# usblcd.net
KiCad netlist of a schematic drawn in EAGLE
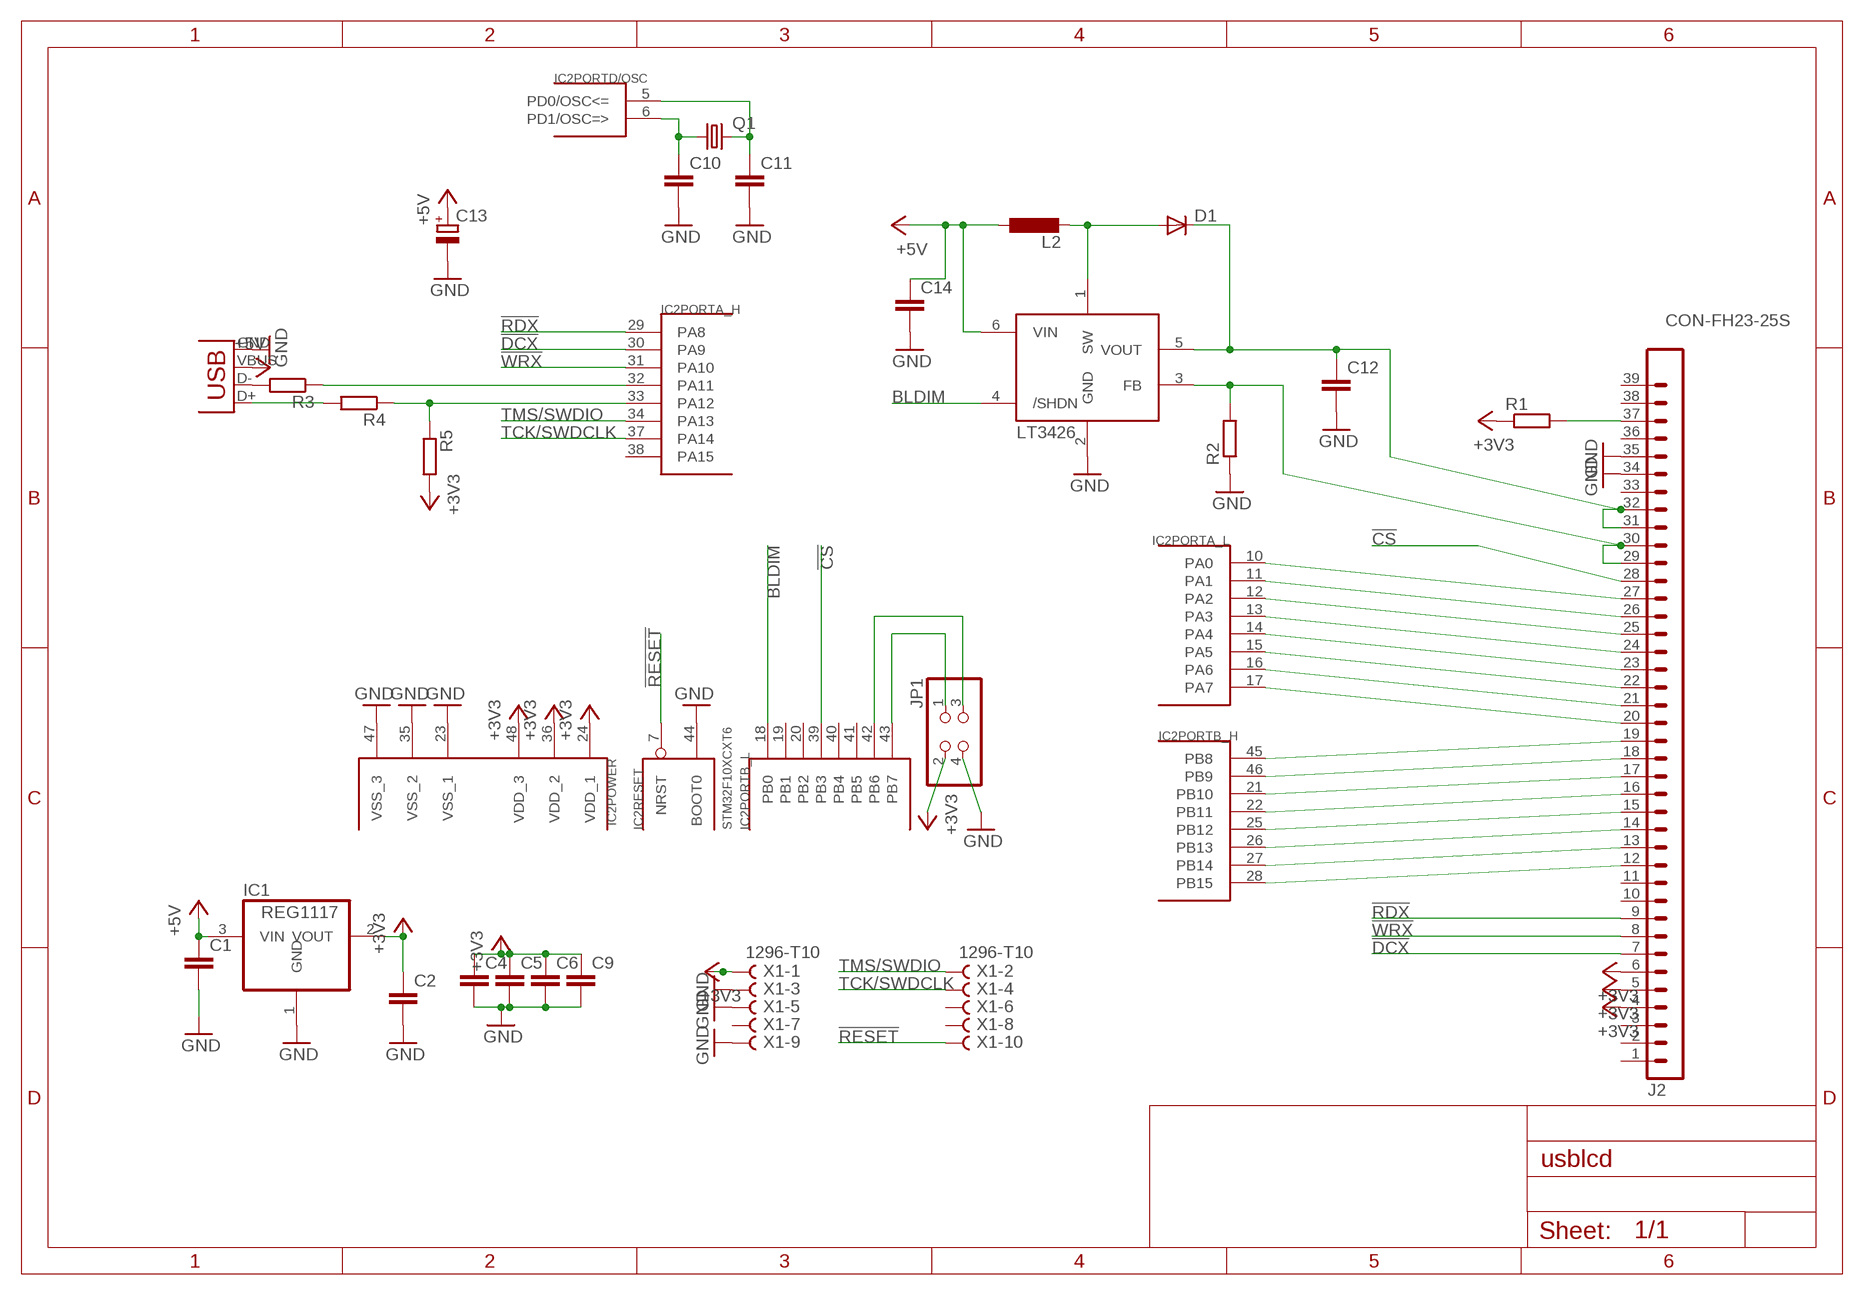
[diagram p0: schematic, sheet 1]

(export (version "E")
  (design (tool "Eeschema 10.0.6"))
  (components
    (comp (ref "C1")
      (value "C-EUC0603")
      (footprint "eagle-import:C0603")
      (libsource (lib "eagle-import") (part "C-EUC0603"))
    )
    (comp (ref "C2")
      (value "C-EUC0603")
      (footprint "eagle-import:C0603")
      (libsource (lib "eagle-import") (part "C-EUC0603"))
    )
    (comp (ref "C4")
      (value "C-EUC0603")
      (footprint "eagle-import:C0603")
      (libsource (lib "eagle-import") (part "C-EUC0603"))
    )
    (comp (ref "C5")
      (value "C-EUC0805")
      (footprint "eagle-import:C0805")
      (libsource (lib "eagle-import") (part "C-EUC0805"))
    )
    (comp (ref "C6")
      (value "C-EUC0603")
      (footprint "eagle-import:C0603")
      (libsource (lib "eagle-import") (part "C-EUC0603"))
    )
    (comp (ref "C9")
      (value "C-EUC0603")
      (footprint "eagle-import:C0603")
      (libsource (lib "eagle-import") (part "C-EUC0603"))
    )
    (comp (ref "C10")
      (value "C-EUC0603")
      (footprint "eagle-import:C0603")
      (libsource (lib "eagle-import") (part "C-EUC0603"))
    )
    (comp (ref "C11")
      (value "C-EUC0603")
      (footprint "eagle-import:C0603")
      (libsource (lib "eagle-import") (part "C-EUC0603"))
    )
    (comp (ref "C12")
      (value "C-EUC0805")
      (footprint "eagle-import:C0805")
      (libsource (lib "eagle-import") (part "C-EUC0805"))
    )
    (comp (ref "C13")
      (value "CPOL-EUC")
      (footprint "eagle-import:PANASONIC_C")
      (libsource (lib "eagle-import") (part "CPOL-EUC"))
    )
    (comp (ref "C14")
      (value "C-EUC0603")
      (footprint "eagle-import:C0603")
      (libsource (lib "eagle-import") (part "C-EUC0603"))
    )
    (comp (ref "D1")
      (value "DIODE-SOD323-W")
      (footprint "eagle-import:SOD323-W")
      (libsource (lib "eagle-import") (part "DIODE-SOD323-W"))
    )
    (comp (ref "IC1")
      (value "REG1117")
      (footprint "eagle-import:SOT223")
      (libsource (lib "eagle-import") (part "REG1117"))
    )
    (comp (ref "IC2")
      (value "STM32F10XCXT6")
      (footprint "eagle-import:TQFP48")
      (libsource (lib "eagle-import") (part "STM32F10XCXT6"))
    )
    (comp (ref "J2")
      (value "CON-FH23-25S")
      (footprint "eagle-import:FH23-25S")
      (libsource (lib "eagle-import") (part "CON-FH23-25S"))
    )
    (comp (ref "JP1")
      (value "PINHD-2X2_2.54-SMD")
      (footprint "eagle-import:2X02SMD")
      (libsource (lib "eagle-import") (part "PINHD-2X2_2.54-SMD"))
    )
    (comp (ref "L2")
      (value "L-EUL3230M")
      (footprint "eagle-import:L3230M")
      (libsource (lib "eagle-import") (part "L-EUL3230M"))
    )
    (comp (ref "Q1")
      (value "CRYSTALCTS406")
      (footprint "eagle-import:CTS406")
      (libsource (lib "eagle-import") (part "CRYSTALCTS406"))
    )
    (comp (ref "R1")
      (value "R-EU_R0603")
      (footprint "eagle-import:R0603")
      (libsource (lib "eagle-import") (part "R-EU_R0603"))
    )
    (comp (ref "R2")
      (value "R-EU_R0603")
      (footprint "eagle-import:R0603")
      (libsource (lib "eagle-import") (part "R-EU_R0603"))
    )
    (comp (ref "R3")
      (value "R-EU_R0603")
      (footprint "eagle-import:R0603")
      (libsource (lib "eagle-import") (part "R-EU_R0603"))
    )
    (comp (ref "R4")
      (value "R-EU_R0603")
      (footprint "eagle-import:R0603")
      (libsource (lib "eagle-import") (part "R-EU_R0603"))
    )
    (comp (ref "R5")
      (value "R-EU_R0603")
      (footprint "eagle-import:R0603")
      (libsource (lib "eagle-import") (part "R-EU_R0603"))
    )
    (comp (ref "U$4")
      (value "LT3426")
      (footprint "eagle-import:SOT23-6")
      (libsource (lib "eagle-import") (part "LT3426"))
    )
    (comp (ref "X1")
      (value "1296-T10")
      (footprint "eagle-import:1296-10")
      (libsource (lib "eagle-import") (part "1296-T10"))
    )
    (comp (ref "X2")
      (value "USB-MICROB")
      (footprint "eagle-import:USB-MICROB")
      (libsource (lib "eagle-import") (part "USB-MICROB"))
    )
  )
  (nets
    (net (code "1") (name "+3V3") (class "Default")
      (node (ref "C2") (pin "1") (pinfunction "1_1") (pintype "passive"))
      (node (ref "C4") (pin "1") (pinfunction "1_1") (pintype "passive"))
      (node (ref "C5") (pin "1") (pinfunction "1_1") (pintype "passive"))
      (node (ref "C6") (pin "1") (pinfunction "1_1") (pintype "passive"))
      (node (ref "C9") (pin "1") (pinfunction "1_1") (pintype "passive"))
      (node (ref "IC1") (pin "2") (pinfunction "VOUT_2") (pintype "output"))
      (node (ref "IC2") (pin "24") (pinfunction "VDD_1_24") (pintype "power_in"))
      (node (ref "IC2") (pin "36") (pinfunction "VDD_2_36") (pintype "power_in"))
      (node (ref "IC2") (pin "48") (pinfunction "VDD_3_48") (pintype "power_in"))
      (node (ref "J2") (pin "4") (pinfunction "4_4") (pintype "passive"))
      (node (ref "J2") (pin "5") (pinfunction "5_5") (pintype "passive"))
      (node (ref "J2") (pin "6") (pinfunction "6_6") (pintype "passive"))
      (node (ref "JP1") (pin "2") (pinfunction "2_2") (pintype "passive"))
      (node (ref "R1") (pin "1") (pinfunction "1_1") (pintype "passive"))
      (node (ref "R5") (pin "2") (pinfunction "2_2") (pintype "passive"))
      (node (ref "X1") (pin "1") (pinfunction "B_1") (pintype "passive"))
    )
    (net (code "2") (name "+5V") (class "Default")
      (node (ref "C1") (pin "1") (pinfunction "1_1") (pintype "passive"))
      (node (ref "C13") (pin "+") (pinfunction "+_+") (pintype "passive"))
      (node (ref "C14") (pin "1") (pinfunction "1_1") (pintype "passive"))
      (node (ref "IC1") (pin "3") (pinfunction "VIN_3") (pintype "input"))
      (node (ref "L2") (pin "1") (pinfunction "1_1") (pintype "passive"))
      (node (ref "U$4") (pin "6") (pinfunction "VIN_6") (pintype "input"))
      (node (ref "X2") (pin "VBUS") (pinfunction "VBUS_VBUS") (pintype "bidirectional"))
    )
    (net (code "3") (name "/BLDIM") (class "Default")
      (node (ref "IC2") (pin "18") (pinfunction "PB0_18") (pintype "bidirectional"))
      (node (ref "U$4") (pin "4") (pinfunction "/SHDN_4") (pintype "input"))
    )
    (net (code "4") (name "/TCK{slash}SWDCLK") (class "Default")
      (node (ref "IC2") (pin "37") (pinfunction "PA14_37") (pintype "bidirectional"))
      (node (ref "X1") (pin "4") (pinfunction "B_4") (pintype "passive"))
    )
    (net (code "5") (name "/TMS{slash}SWDIO") (class "Default")
      (node (ref "IC2") (pin "34") (pinfunction "PA13_34") (pintype "bidirectional"))
      (node (ref "X1") (pin "2") (pinfunction "B_2") (pintype "passive"))
    )
    (net (code "6") (name "/~{CS}") (class "Default")
      (node (ref "IC2") (pin "39") (pinfunction "PB3_39") (pintype "bidirectional"))
      (node (ref "J2") (pin "28") (pinfunction "28_28") (pintype "passive"))
    )
    (net (code "7") (name "/~{DCX}") (class "Default")
      (node (ref "IC2") (pin "30") (pinfunction "PA9_30") (pintype "bidirectional"))
      (node (ref "J2") (pin "7") (pinfunction "7_7") (pintype "passive"))
    )
    (net (code "8") (name "/~{RDX}") (class "Default")
      (node (ref "IC2") (pin "29") (pinfunction "PA8_29") (pintype "bidirectional"))
      (node (ref "J2") (pin "9") (pinfunction "9_9") (pintype "passive"))
    )
    (net (code "9") (name "/~{RESET}") (class "Default")
      (node (ref "IC2") (pin "7") (pinfunction "NRST_7") (pintype "input"))
      (node (ref "X1") (pin "10") (pinfunction "B_10") (pintype "passive"))
    )
    (net (code "10") (name "/~{WRX}") (class "Default")
      (node (ref "IC2") (pin "31") (pinfunction "PA10_31") (pintype "bidirectional"))
      (node (ref "J2") (pin "8") (pinfunction "8_8") (pintype "passive"))
    )
    (net (code "11") (name "GND") (class "Default")
      (node (ref "C1") (pin "2") (pinfunction "2_2") (pintype "passive"))
      (node (ref "C10") (pin "2") (pinfunction "2_2") (pintype "passive"))
      (node (ref "C11") (pin "2") (pinfunction "2_2") (pintype "passive"))
      (node (ref "C12") (pin "2") (pinfunction "2_2") (pintype "passive"))
      (node (ref "C13") (pin "-") (pinfunction "-_-") (pintype "passive"))
      (node (ref "C14") (pin "2") (pinfunction "2_2") (pintype "passive"))
      (node (ref "C2") (pin "2") (pinfunction "2_2") (pintype "passive"))
      (node (ref "C4") (pin "2") (pinfunction "2_2") (pintype "passive"))
      (node (ref "C5") (pin "2") (pinfunction "2_2") (pintype "passive"))
      (node (ref "C6") (pin "2") (pinfunction "2_2") (pintype "passive"))
      (node (ref "C9") (pin "2") (pinfunction "2_2") (pintype "passive"))
      (node (ref "IC1") (pin "1") (pinfunction "GND_1") (pintype "power_in"))
      (node (ref "IC2") (pin "23") (pinfunction "VSS_1_23") (pintype "power_in"))
      (node (ref "IC2") (pin "35") (pinfunction "VSS_2_35") (pintype "power_in"))
      (node (ref "IC2") (pin "44") (pinfunction "BOOT0_44") (pintype "input"))
      (node (ref "IC2") (pin "47") (pinfunction "VSS_3_47") (pintype "power_in"))
      (node (ref "J2") (pin "34") (pinfunction "34_34") (pintype "passive"))
      (node (ref "J2") (pin "35") (pinfunction "35_35") (pintype "passive"))
      (node (ref "JP1") (pin "4") (pinfunction "4_4") (pintype "passive"))
      (node (ref "R2") (pin "1") (pinfunction "1_1") (pintype "passive"))
      (node (ref "U$4") (pin "2") (pinfunction "GND_2") (pintype "power_in"))
      (node (ref "X1") (pin "3") (pinfunction "B_3") (pintype "passive"))
      (node (ref "X1") (pin "5") (pinfunction "B_5") (pintype "passive"))
      (node (ref "X1") (pin "9") (pinfunction "B_9") (pintype "passive"))
      (node (ref "X2") (pin "GND") (pinfunction "GND_GND") (pintype "bidirectional"))
    )
    (net (code "12") (name "Net-(IC2B-PA11)") (class "Default")
      (node (ref "IC2") (pin "32") (pinfunction "PA11_32") (pintype "bidirectional"))
      (node (ref "R3") (pin "1") (pinfunction "1_1") (pintype "passive"))
    )
    (net (code "13") (name "Net-(IC2B-PA12)") (class "Default")
      (node (ref "IC2") (pin "33") (pinfunction "PA12_33") (pintype "bidirectional"))
      (node (ref "R4") (pin "1") (pinfunction "1_1") (pintype "passive"))
      (node (ref "R5") (pin "1") (pinfunction "1_1") (pintype "passive"))
    )
    (net (code "14") (name "Net-(IC2C-PA0)") (class "Default")
      (node (ref "IC2") (pin "10") (pinfunction "PA0_10") (pintype "bidirectional"))
      (node (ref "J2") (pin "27") (pinfunction "27_27") (pintype "passive"))
    )
    (net (code "15") (name "Net-(IC2C-PA1)") (class "Default")
      (node (ref "IC2") (pin "11") (pinfunction "PA1_11") (pintype "bidirectional"))
      (node (ref "J2") (pin "26") (pinfunction "26_26") (pintype "passive"))
    )
    (net (code "16") (name "Net-(IC2C-PA2)") (class "Default")
      (node (ref "IC2") (pin "12") (pinfunction "PA2_12") (pintype "bidirectional"))
      (node (ref "J2") (pin "25") (pinfunction "25_25") (pintype "passive"))
    )
    (net (code "17") (name "Net-(IC2C-PA3)") (class "Default")
      (node (ref "IC2") (pin "13") (pinfunction "PA3_13") (pintype "bidirectional"))
      (node (ref "J2") (pin "24") (pinfunction "24_24") (pintype "passive"))
    )
    (net (code "18") (name "Net-(IC2C-PA4)") (class "Default")
      (node (ref "IC2") (pin "14") (pinfunction "PA4_14") (pintype "bidirectional"))
      (node (ref "J2") (pin "23") (pinfunction "23_23") (pintype "passive"))
    )
    (net (code "19") (name "Net-(IC2C-PA5)") (class "Default")
      (node (ref "IC2") (pin "15") (pinfunction "PA5_15") (pintype "bidirectional"))
      (node (ref "J2") (pin "22") (pinfunction "22_22") (pintype "passive"))
    )
    (net (code "20") (name "Net-(IC2C-PA6)") (class "Default")
      (node (ref "IC2") (pin "16") (pinfunction "PA6_16") (pintype "bidirectional"))
      (node (ref "J2") (pin "21") (pinfunction "21_21") (pintype "passive"))
    )
    (net (code "21") (name "Net-(IC2C-PA7)") (class "Default")
      (node (ref "IC2") (pin "17") (pinfunction "PA7_17") (pintype "bidirectional"))
      (node (ref "J2") (pin "20") (pinfunction "20_20") (pintype "passive"))
    )
    (net (code "22") (name "Net-(IC2D-PB8)") (class "Default")
      (node (ref "IC2") (pin "45") (pinfunction "PB8_45") (pintype "bidirectional"))
      (node (ref "J2") (pin "19") (pinfunction "19_19") (pintype "passive"))
    )
    (net (code "23") (name "Net-(IC2D-PB9)") (class "Default")
      (node (ref "IC2") (pin "46") (pinfunction "PB9_46") (pintype "bidirectional"))
      (node (ref "J2") (pin "18") (pinfunction "18_18") (pintype "passive"))
    )
    (net (code "24") (name "Net-(IC2D-PB10)") (class "Default")
      (node (ref "IC2") (pin "21") (pinfunction "PB10_21") (pintype "bidirectional"))
      (node (ref "J2") (pin "17") (pinfunction "17_17") (pintype "passive"))
    )
    (net (code "25") (name "Net-(IC2D-PB11)") (class "Default")
      (node (ref "IC2") (pin "22") (pinfunction "PB11_22") (pintype "bidirectional"))
      (node (ref "J2") (pin "16") (pinfunction "16_16") (pintype "passive"))
    )
    (net (code "26") (name "Net-(IC2D-PB12)") (class "Default")
      (node (ref "IC2") (pin "25") (pinfunction "PB12_25") (pintype "bidirectional"))
      (node (ref "J2") (pin "15") (pinfunction "15_15") (pintype "passive"))
    )
    (net (code "27") (name "Net-(IC2D-PB13)") (class "Default")
      (node (ref "IC2") (pin "26") (pinfunction "PB13_26") (pintype "bidirectional"))
      (node (ref "J2") (pin "14") (pinfunction "14_14") (pintype "passive"))
    )
    (net (code "28") (name "Net-(IC2D-PB14)") (class "Default")
      (node (ref "IC2") (pin "27") (pinfunction "PB14_27") (pintype "bidirectional"))
      (node (ref "J2") (pin "13") (pinfunction "13_13") (pintype "passive"))
    )
    (net (code "29") (name "Net-(IC2D-PB15)") (class "Default")
      (node (ref "IC2") (pin "28") (pinfunction "PB15_28") (pintype "bidirectional"))
      (node (ref "J2") (pin "12") (pinfunction "12_12") (pintype "passive"))
    )
    (net (code "30") (name "Net-(IC2E-PB6)") (class "Default")
      (node (ref "IC2") (pin "42") (pinfunction "PB6_42") (pintype "bidirectional"))
      (node (ref "JP1") (pin "3") (pinfunction "3_3") (pintype "passive"))
    )
    (net (code "31") (name "Net-(IC2E-PB7)") (class "Default")
      (node (ref "IC2") (pin "43") (pinfunction "PB7_43") (pintype "bidirectional"))
      (node (ref "JP1") (pin "1") (pinfunction "1_1") (pintype "passive"))
    )
    (net (code "32") (name "Net-(IC2G-PD0{slash}OSC<=)") (class "Default")
      (node (ref "C11") (pin "1") (pinfunction "1_1") (pintype "passive"))
      (node (ref "IC2") (pin "5") (pinfunction "PD0/OSC<=_5") (pintype "bidirectional"))
      (node (ref "Q1") (pin "3") (pinfunction "2_3") (pintype "passive"))
    )
    (net (code "33") (name "Net-(IC2G-PD1{slash}OSC=>)") (class "Default")
      (node (ref "C10") (pin "1") (pinfunction "1_1") (pintype "passive"))
      (node (ref "IC2") (pin "6") (pinfunction "PD1/OSC=>_6") (pintype "bidirectional"))
      (node (ref "Q1") (pin "1") (pinfunction "1_1") (pintype "passive"))
    )
    (net (code "34") (name "Net-(J2-Pad37)") (class "Default")
      (node (ref "J2") (pin "37") (pinfunction "37_37") (pintype "passive"))
      (node (ref "R1") (pin "2") (pinfunction "2_2") (pintype "passive"))
    )
    (net (code "35") (name "Net-(R3-Pad2)") (class "Default")
      (node (ref "R3") (pin "2") (pinfunction "2_2") (pintype "passive"))
      (node (ref "X2") (pin "D-") (pinfunction "D-_D-") (pintype "bidirectional"))
    )
    (net (code "36") (name "Net-(R4-Pad2)") (class "Default")
      (node (ref "R4") (pin "2") (pinfunction "2_2") (pintype "passive"))
      (node (ref "X2") (pin "D+") (pinfunction "D+_D+") (pintype "bidirectional"))
    )
    (net (code "37") (name "Net-(U$4-FB)") (class "Default")
      (node (ref "J2") (pin "29") (pinfunction "29_29") (pintype "passive"))
      (node (ref "J2") (pin "30") (pinfunction "30_30") (pintype "passive"))
      (node (ref "R2") (pin "2") (pinfunction "2_2") (pintype "passive"))
      (node (ref "U$4") (pin "3") (pinfunction "FB_3") (pintype "input"))
    )
    (net (code "38") (name "Net-(U$4-SW)") (class "Default")
      (node (ref "D1") (pin "A") (pinfunction "A_A") (pintype "passive"))
      (node (ref "L2") (pin "2") (pinfunction "2_2") (pintype "passive"))
      (node (ref "U$4") (pin "1") (pinfunction "SW_1") (pintype "output"))
    )
    (net (code "39") (name "Net-(U$4-VOUT)") (class "Default")
      (node (ref "C12") (pin "1") (pinfunction "1_1") (pintype "passive"))
      (node (ref "D1") (pin "C") (pinfunction "C_C") (pintype "passive"))
      (node (ref "J2") (pin "31") (pinfunction "31_31") (pintype "passive"))
      (node (ref "J2") (pin "32") (pinfunction "32_32") (pintype "passive"))
      (node (ref "U$4") (pin "5") (pinfunction "VOUT_5") (pintype "output"))
    )
    (net (code "40") (name "unconnected-(IC2B-PA15-Pad38)") (class "Default")
      (node (ref "IC2") (pin "38") (pinfunction "PA15_38") (pintype "bidirectional"))
    )
    (net (code "41") (name "unconnected-(IC2E-PB1-Pad19)") (class "Default")
      (node (ref "IC2") (pin "19") (pinfunction "PB1_19") (pintype "bidirectional"))
    )
    (net (code "42") (name "unconnected-(IC2E-PB2-Pad20)") (class "Default")
      (node (ref "IC2") (pin "20") (pinfunction "PB2_20") (pintype "bidirectional"))
    )
    (net (code "43") (name "unconnected-(IC2E-PB4-Pad40)") (class "Default")
      (node (ref "IC2") (pin "40") (pinfunction "PB4_40") (pintype "bidirectional"))
    )
    (net (code "44") (name "unconnected-(IC2E-PB5-Pad41)") (class "Default")
      (node (ref "IC2") (pin "41") (pinfunction "PB5_41") (pintype "bidirectional"))
    )
    (net (code "45") (name "unconnected-(J2-Pad1)") (class "Default")
      (node (ref "J2") (pin "1") (pinfunction "1_1") (pintype "passive"))
    )
    (net (code "46") (name "unconnected-(J2-Pad2)") (class "Default")
      (node (ref "J2") (pin "2") (pinfunction "2_2") (pintype "passive"))
    )
    (net (code "47") (name "unconnected-(J2-Pad3)") (class "Default")
      (node (ref "J2") (pin "3") (pinfunction "3_3") (pintype "passive"))
    )
    (net (code "48") (name "unconnected-(J2-Pad10)") (class "Default")
      (node (ref "J2") (pin "10") (pinfunction "10_10") (pintype "passive"))
    )
    (net (code "49") (name "unconnected-(J2-Pad11)") (class "Default")
      (node (ref "J2") (pin "11") (pinfunction "11_11") (pintype "passive"))
    )
    (net (code "50") (name "unconnected-(J2-Pad33)") (class "Default")
      (node (ref "J2") (pin "33") (pinfunction "33_33") (pintype "passive"))
    )
    (net (code "51") (name "unconnected-(J2-Pad36)") (class "Default")
      (node (ref "J2") (pin "36") (pinfunction "36_36") (pintype "passive"))
    )
    (net (code "52") (name "unconnected-(J2-Pad38)") (class "Default")
      (node (ref "J2") (pin "38") (pinfunction "38_38") (pintype "passive"))
    )
    (net (code "53") (name "unconnected-(J2-Pad39)") (class "Default")
      (node (ref "J2") (pin "39") (pinfunction "39_39") (pintype "passive"))
    )
    (net (code "54") (name "unconnected-(X1G-B-Pad6)") (class "Default")
      (node (ref "X1") (pin "6") (pinfunction "B_6") (pintype "passive"))
    )
    (net (code "55") (name "unconnected-(X1H-B-Pad7)") (class "Default")
      (node (ref "X1") (pin "7") (pinfunction "B_7") (pintype "passive"))
    )
    (net (code "56") (name "unconnected-(X1I-B-Pad8)") (class "Default")
      (node (ref "X1") (pin "8") (pinfunction "B_8") (pintype "passive"))
    )
  )
)
